# Power_Management.net
KiCad netlist of a schematic drawn in Altium Designer
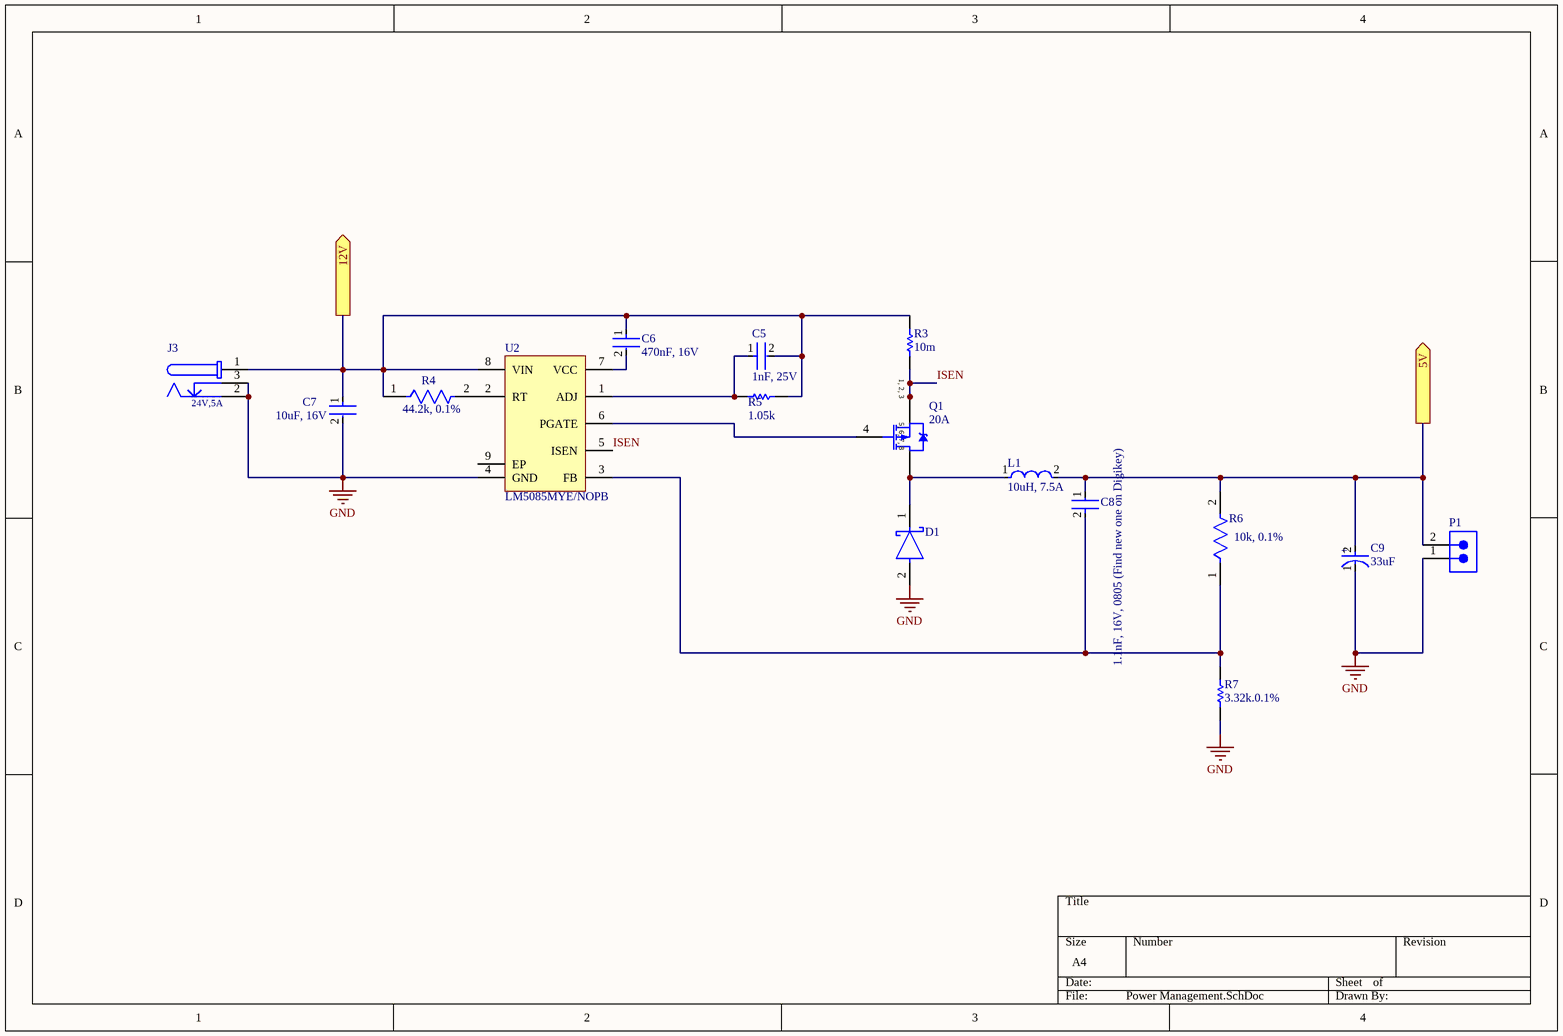
[diagram p0: Power Management.SchDoc]

(export (version "E")
  (design (tool "Eeschema 10.0.6"))
  (components
    (comp (ref "C5")
      (value "1nF, 25V")
      (footprint "FP-C0805C-DN-MFG")
      (description "CAP CER 1000PF 25V X7R 0805")
      (fields
        (field (name "MANUFACTURER") "KEMET")
        (field (name "OCTOPART") "https://octopart.com/c0805c102k3ractu-kemet-16646211")
      )
      (libsource (lib "Altium Content Vault") (part "b4654b650e69147ec39a6b967a45e02"))
    )
    (comp (ref "C6")
      (value "470nF, 16V")
      (footprint "FP-0805-L_2_01_0_2-W_1_25-IPC_B")
      (description "General Purpose Ceramic Capacitor, 0805, 470nF, 10%, X7R, 15%, 16V")
      (fields (field (name "VOLTAGE") "16V") (field (name "TOLERANCE") "10%"))
      (libsource (lib "Altium Content Vault") (part "b4654b650e69147ec39a6b967a45e02"))
    )
    (comp (ref "C7")
      (value "10uF, 16V")
      (footprint "FP-C2012-125-0_2-MFG")
      (description "Multilayer Ceramic Capacitors 10μF ±10% 16V X6S SMD 0805")
      (fields (field (name "TOLERANCE") "10%"))
      (libsource (lib "Altium Content Vault") (part "b4654b650e69147ec39a6b967a45e02"))
    )
    (comp (ref "C8")
      (value "1.1nF, 16V, 0805 (Find new one on Digikey)")
      (footprint "FP-GRM216-0_1-MFG")
      (description "Chip Multilayer Ceramic Capacitors for General Purpose, 0805, 1100pF, C0G, 30ppm/°C, 5%, 100V")
      (fields (field (name "TOLERANCE") "5%"))
      (libsource (lib "Altium Content Vault") (part "236180d848d6139a670b325ea6854c9"))
    )
    (comp (ref "C9")
      (value "33uF")
      (footprint "FP-TAJB-MFG")
      (description "33uF 6.3V  ±10% 2.2Ω 1210  SMD Tantalum Capacitor")
      (fields (field (name "TOLERANCE") "20%") (field (name "VOLTAGE") "10V"))
      (libsource (lib "Altium Content Vault") (part "203bc49f2ac43e59fd269a8c329ed05"))
    )
    (comp (ref "D1")
      (value "~")
      (footprint "FP-95402-MFG")
      (description "Diode Schottky 40V 3A Surface Mount DO-214AB (SMC)")
      (fields (field (name "MANUFACTURER") "Vishay"))
      (libsource (lib "Altium Content Vault") (part "1d6ec82d83fb6aee721767c19dac4b9"))
    )
    (comp (ref "J3")
      (value "24V,5A")
      (footprint "694106301002")
      (description "DC Power Jack Connector WR-DC, Male, Right Angled, THT, 5 A, 24 V")
      (fields
        (field (name "MANUFACTURER") "Wurth Elektronik")
        (field (name "PART NUMBER") "694106301002")
        (field (name "PUBLISHER") "WurthElektronik")
      )
      (libsource (lib "Altium Content Vault") (part "WE-JACK-2CD3-RN"))
    )
    (comp (ref "L1")
      (value "10uH, 7.5A")
      (footprint "FP-IHLP-4040DZ-FP_3_124x3-MFG")
      (description "Commercial Inductors, Low DCR Series 10uH 7.5A 30.5mΩ 20%")
      (fields (field (name "TOLERANCE") "20%"))
      (libsource (lib "Altium Content Vault") (part "725321dda6339637d4d059423bc1c3c"))
    )
    (comp (ref "P1")
      (value "TSW-102-26-G-S")
      (footprint "SMTC-TSW-102-26-XX-S")
      (description "0.025\" SQ Post Header, Through-hole, Vertical, -55 to 125 degC, 2.54 mm Pitch, 2-Pin, Male, RoHS")
      (fields (field (name "MANUFACTURER") "Samtec"))
      (libsource (lib "Altium Content Vault") (part "SMTC-TSW-102-X-X-S-X"))
    )
    (comp (ref "Q1")
      (value "20A")
      (footprint "ONSC-SOIC-8-751-07_V")
      (description "Power MOSFET, -10 A, -20 V, Single P-Channel Enhancement-Mode, 8-Pin SOIC, Pb-Free, Tape and Reel")
      (fields (field (name "PARTNUMBER") "NTMS10P02R2G") (field (name "MANUFACTURER") "On Semiconductor"))
      (libsource (lib "Altium Content Vault") (part "ONSC-PMOS-8_G"))
    )
    (comp (ref "R3")
      (value "10m")
      (footprint "RESC2013X75X55NL20T20")
      (fields (field (name "PART NUMBER") "ERJ-6BWFR010V") (field (name "MANUFACTURER") "Panasonic"))
      (libsource (lib "Altium Content Vault") (part "RES"))
    )
    (comp (ref "R4")
      (value "44.2k, 0.1%")
      (footprint "FP-RT0805-MFG")
      (description "RT0805 44.2KΩ 0.125W 25 ppm/°C 0.25%")
      (fields (field (name "OCTOPART") "https://octopart.com/rt0805brd0744k2l-yageo-1480106"))
      (libsource (lib "Altium Content Vault") (part "1029c3af85768c4190bb7ad29bc67b5"))
    )
    (comp (ref "R5")
      (value "1.05k")
      (footprint "RESC2013X70X40NL20T20")
      (fields (field (name "MANUFACTURER") "Panasonic") (field (name "PART NUMBER") "ERJ-6ENF1051V"))
      (libsource (lib "Altium Content Vault") (part "RES"))
    )
    (comp (ref "R6")
      (value "10k, 0.1%")
      (footprint "FP-MCU0805-IPC_C")
      (description "RES 1.05K OHM 0.5% 1/5W 0805")
      (fields (field (name "TOLERANCE") "0.1%"))
      (libsource (lib "Altium Content Vault") (part "1029c3af85768c4190bb7ad29bc67b5"))
    )
    (comp (ref "R7")
      (value "3.32k.0.1%")
      (footprint "RESC2013X55X40NL15T20")
      (fields (field (name "PART NUMBER") "TNPW08053K32BEEN") (field (name "MANUFACTURER") "Vishay Dale"))
      (libsource (lib "Altium Content Vault") (part "RES"))
    )
    (comp (ref "U2")
      (value "LM5085MYE/NOPB")
      (footprint "DGN0008A_N")
      (description "75V Constant On-Time PFET Buck Switching Controller, 8-pin eMSOP, Pb-Free")
      (fields (field (name "MANUFACTURER") "Texas Instruments"))
      (libsource (lib "Altium Content Vault") (part "PM-SWREG-LM5085-9"))
    )
  )
  (nets
    (net (code "1") (name "/5V") (class "Default")
      (node (ref "C8") (pin "1") (pinfunction "1_1") (pintype "passive"))
      (node (ref "C9") (pin "2") (pinfunction "A_2") (pintype "passive"))
      (node (ref "L1") (pin "2") (pinfunction "2_2") (pintype "passive"))
      (node (ref "P1") (pin "2") (pinfunction "2_2") (pintype "passive"))
      (node (ref "R6") (pin "2") (pinfunction "2_2") (pintype "passive"))
    )
    (net (code "2") (name "/12V") (class "Default")
      (node (ref "C5") (pin "2") (pinfunction "2_2") (pintype "passive"))
      (node (ref "C6") (pin "1") (pinfunction "1_1") (pintype "passive"))
      (node (ref "C7") (pin "1") (pinfunction "1_1") (pintype "passive"))
      (node (ref "J3") (pin "1") (pinfunction "1_1") (pintype "passive"))
      (node (ref "R3") (pin "2") (pinfunction "2_2") (pintype "passive"))
      (node (ref "R4") (pin "1") (pinfunction "1_1") (pintype "passive"))
      (node (ref "R5") (pin "2") (pinfunction "2_2") (pintype "passive"))
      (node (ref "U2") (pin "8") (pinfunction "VIN_8") (pintype "passive"))
    )
    (net (code "3") (name "/ISEN") (class "Default")
      (node (ref "Q1") (pin "1") (pinfunction "S_1") (pintype "passive"))
      (node (ref "Q1") (pin "2") (pinfunction "S_2") (pintype "passive"))
      (node (ref "Q1") (pin "3") (pinfunction "S_3") (pintype "passive"))
      (node (ref "R3") (pin "1") (pinfunction "1_1") (pintype "passive"))
      (node (ref "U2") (pin "5") (pinfunction "ISEN_5") (pintype "passive"))
    )
    (net (code "4") (name "GND") (class "Default")
      (node (ref "C7") (pin "2") (pinfunction "2_2") (pintype "passive"))
      (node (ref "C9") (pin "1") (pinfunction "C_1") (pintype "passive"))
      (node (ref "D1") (pin "2") (pinfunction "A_2") (pintype "passive"))
      (node (ref "J3") (pin "2") (pinfunction "2_2") (pintype "passive"))
      (node (ref "J3") (pin "3") (pinfunction "3_3") (pintype "passive"))
      (node (ref "P1") (pin "1") (pinfunction "1_1") (pintype "passive"))
      (node (ref "R7") (pin "1") (pinfunction "1_1") (pintype "passive"))
      (node (ref "U2") (pin "4") (pinfunction "GND_4") (pintype "power_in"))
    )
    (net (code "5") (name "Net-(D1-C)") (class "Default")
      (node (ref "D1") (pin "1") (pinfunction "C_1") (pintype "passive"))
      (node (ref "L1") (pin "1") (pinfunction "1_1") (pintype "passive"))
      (node (ref "Q1") (pin "5") (pinfunction "D_5") (pintype "passive"))
      (node (ref "Q1") (pin "6") (pinfunction "D_6") (pintype "passive"))
      (node (ref "Q1") (pin "7") (pinfunction "D_7") (pintype "passive"))
      (node (ref "Q1") (pin "8") (pinfunction "D_8") (pintype "passive"))
    )
    (net (code "6") (name "Net-(Q1-G)") (class "Default")
      (node (ref "Q1") (pin "4") (pinfunction "G_4") (pintype "passive"))
      (node (ref "U2") (pin "6") (pinfunction "PGATE_6") (pintype "passive"))
    )
    (net (code "7") (name "Net-(U2-ADJ)") (class "Default")
      (node (ref "C5") (pin "1") (pinfunction "1_1") (pintype "passive"))
      (node (ref "R5") (pin "1") (pinfunction "1_1") (pintype "passive"))
      (node (ref "U2") (pin "1") (pinfunction "ADJ_1") (pintype "passive"))
    )
    (net (code "8") (name "Net-(U2-FB)") (class "Default")
      (node (ref "C8") (pin "2") (pinfunction "2_2") (pintype "passive"))
      (node (ref "R6") (pin "1") (pinfunction "1_1") (pintype "passive"))
      (node (ref "R7") (pin "2") (pinfunction "2_2") (pintype "passive"))
      (node (ref "U2") (pin "3") (pinfunction "FB_3") (pintype "passive"))
    )
    (net (code "9") (name "Net-(U2-RT)") (class "Default")
      (node (ref "R4") (pin "2") (pinfunction "2_2") (pintype "passive"))
      (node (ref "U2") (pin "2") (pinfunction "RT_2") (pintype "passive"))
    )
    (net (code "10") (name "Net-(U2-VCC)") (class "Default")
      (node (ref "C6") (pin "2") (pinfunction "2_2") (pintype "passive"))
      (node (ref "U2") (pin "7") (pinfunction "VCC_7") (pintype "power_in"))
    )
    (net (code "11") (name "unconnected-(U2-EP-Pad9)") (class "Default")
      (node (ref "U2") (pin "9") (pinfunction "EP_9") (pintype "passive"))
    )
  )
)
